# heartrate.net
KiCad netlist of a schematic drawn in EAGLE
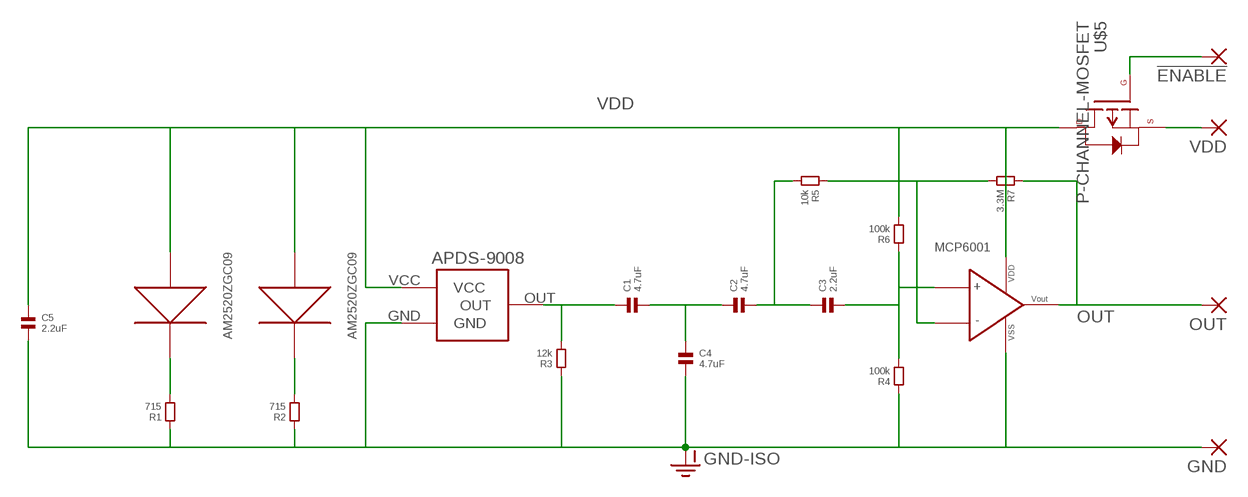
[diagram p0: schematic, sheet 1]

(export (version "E")
  (design (tool "Eeschema 10.0.6"))
  (components
    (comp (ref "!ENABLE")
      (value "SMD2")
      (footprint "eagle-import:SMD1,27-2,54")
      (libsource (lib "eagle-import") (part "SMD2"))
    )
    (comp (ref "C1")
      (value "4.7uF")
      (footprint "eagle-import:0402")
      (libsource (lib "eagle-import") (part "CAPACITOR.0402"))
    )
    (comp (ref "C2")
      (value "4.7uF")
      (footprint "eagle-import:0402")
      (libsource (lib "eagle-import") (part "CAPACITOR.0402"))
    )
    (comp (ref "C3")
      (value "2.2uF")
      (footprint "eagle-import:0402")
      (libsource (lib "eagle-import") (part "CAPACITOR.0402"))
    )
    (comp (ref "C4")
      (value "4.7uF")
      (footprint "eagle-import:0402")
      (libsource (lib "eagle-import") (part "CAPACITOR.0402"))
    )
    (comp (ref "C5")
      (value "2.2uF")
      (footprint "eagle-import:0402")
      (libsource (lib "eagle-import") (part "CAPACITOR.0402"))
    )
    (comp (ref "GND")
      (value "SMD2")
      (footprint "eagle-import:SMD1,27-2,54")
      (libsource (lib "eagle-import") (part "SMD2"))
    )
    (comp (ref "OUT")
      (value "SMD2")
      (footprint "eagle-import:SMD1,27-2,54")
      (libsource (lib "eagle-import") (part "SMD2"))
    )
    (comp (ref "R1")
      (value "715")
      (footprint "eagle-import:0402")
      (libsource (lib "eagle-import") (part "RESISTOR.0402"))
    )
    (comp (ref "R2")
      (value "715")
      (footprint "eagle-import:0402")
      (libsource (lib "eagle-import") (part "RESISTOR.0402"))
    )
    (comp (ref "R3")
      (value "12k")
      (footprint "eagle-import:0402")
      (libsource (lib "eagle-import") (part "RESISTOR.0402"))
    )
    (comp (ref "R4")
      (value "100k")
      (footprint "eagle-import:0402")
      (libsource (lib "eagle-import") (part "RESISTOR.0402"))
    )
    (comp (ref "R5")
      (value "10k")
      (footprint "eagle-import:0402")
      (libsource (lib "eagle-import") (part "RESISTOR.0402"))
    )
    (comp (ref "R6")
      (value "100k")
      (footprint "eagle-import:0402")
      (libsource (lib "eagle-import") (part "RESISTOR.0402"))
    )
    (comp (ref "R7")
      (value "3.3M")
      (footprint "eagle-import:0402")
      (libsource (lib "eagle-import") (part "RESISTOR.0402"))
    )
    (comp (ref "U$1")
      (value "DSAH3717")
      (footprint "eagle-import:DSAH3717")
      (libsource (lib "eagle-import") (part "DSAH3717"))
    )
    (comp (ref "U$2")
      (value "DSAH3717")
      (footprint "eagle-import:DSAH3717")
      (libsource (lib "eagle-import") (part "DSAH3717"))
    )
    (comp (ref "U$3")
      (value "APDS-9008")
      (footprint "eagle-import:APDS-9008")
      (libsource (lib "eagle-import") (part "APDS-9008"))
    )
    (comp (ref "U$4")
      (value "MCP6001")
      (footprint "eagle-import:SOT23-5")
      (libsource (lib "eagle-import") (part "MCP6001"))
    )
    (comp (ref "U$5")
      (value "P-CHANNEL-MOSFET")
      (footprint "eagle-import:SOT23-3")
      (libsource (lib "eagle-import") (part "P-CHANNEL-MOSFET"))
    )
    (comp (ref "VDD")
      (value "SMD2")
      (footprint "eagle-import:SMD1,27-2,54")
      (libsource (lib "eagle-import") (part "SMD2"))
    )
  )
  (nets
    (net (code "1") (name "/OUT") (class "Default")
      (node (ref "OUT") (pin "1") (pinfunction "P_1") (pintype "passive"))
      (node (ref "R7") (pin "1") (pinfunction "1_1") (pintype "bidirectional"))
      (node (ref "U$4") (pin "VOUT") (pinfunction "VOUT_VOUT") (pintype "bidirectional"))
    )
    (net (code "2") (name "/VDD") (class "Default")
      (node (ref "C5") (pin "1") (pinfunction "1_1") (pintype "bidirectional"))
      (node (ref "R6") (pin "2") (pinfunction "2_2") (pintype "bidirectional"))
      (node (ref "U$1") (pin "V") (pinfunction "VDD_V") (pintype "power_in"))
      (node (ref "U$2") (pin "V") (pinfunction "VDD_V") (pintype "power_in"))
      (node (ref "U$3") (pin "VCC") (pinfunction "VCC_VCC") (pintype "bidirectional"))
      (node (ref "U$4") (pin "VDD") (pinfunction "VDD_VDD") (pintype "bidirectional"))
      (node (ref "U$5") (pin "3") (pinfunction "D_3") (pintype "passive"))
    )
    (net (code "3") (name "GND-ISO") (class "Default")
      (node (ref "C4") (pin "2") (pinfunction "2_2") (pintype "bidirectional"))
      (node (ref "C5") (pin "2") (pinfunction "2_2") (pintype "bidirectional"))
      (node (ref "GND") (pin "1") (pinfunction "P_1") (pintype "passive"))
      (node (ref "R1") (pin "1") (pinfunction "1_1") (pintype "bidirectional"))
      (node (ref "R2") (pin "1") (pinfunction "1_1") (pintype "bidirectional"))
      (node (ref "R3") (pin "1") (pinfunction "1_1") (pintype "bidirectional"))
      (node (ref "R4") (pin "1") (pinfunction "1_1") (pintype "bidirectional"))
      (node (ref "U$3") (pin "GND") (pinfunction "GND_GND") (pintype "bidirectional"))
      (node (ref "U$4") (pin "VSS") (pinfunction "VSS_VSS") (pintype "bidirectional"))
    )
    (net (code "4") (name "Net-(!ENABLE-P)") (class "Default")
      (node (ref "!ENABLE") (pin "1") (pinfunction "P_1") (pintype "passive"))
      (node (ref "U$5") (pin "1") (pinfunction "G_1") (pintype "passive"))
    )
    (net (code "5") (name "Net-(C1-Pad1)") (class "Default")
      (node (ref "C1") (pin "1") (pinfunction "1_1") (pintype "bidirectional"))
      (node (ref "R3") (pin "2") (pinfunction "2_2") (pintype "bidirectional"))
      (node (ref "U$3") (pin "OUT") (pinfunction "OUT_OUT") (pintype "bidirectional"))
    )
    (net (code "6") (name "Net-(C1-Pad2)") (class "Default")
      (node (ref "C1") (pin "2") (pinfunction "2_2") (pintype "bidirectional"))
      (node (ref "C2") (pin "1") (pinfunction "1_1") (pintype "bidirectional"))
      (node (ref "C4") (pin "1") (pinfunction "1_1") (pintype "bidirectional"))
    )
    (net (code "7") (name "Net-(C2-Pad2)") (class "Default")
      (node (ref "C2") (pin "2") (pinfunction "2_2") (pintype "bidirectional"))
      (node (ref "C3") (pin "1") (pinfunction "1_1") (pintype "bidirectional"))
      (node (ref "R5") (pin "2") (pinfunction "2_2") (pintype "bidirectional"))
    )
    (net (code "8") (name "Net-(C3-Pad2)") (class "Default")
      (node (ref "C3") (pin "2") (pinfunction "2_2") (pintype "bidirectional"))
      (node (ref "R4") (pin "2") (pinfunction "2_2") (pintype "bidirectional"))
      (node (ref "R6") (pin "1") (pinfunction "1_1") (pintype "bidirectional"))
      (node (ref "U$4") (pin "VIN+") (pinfunction "VIN+_VIN+") (pintype "bidirectional"))
    )
    (net (code "9") (name "Net-(R5-Pad1)") (class "Default")
      (node (ref "R5") (pin "1") (pinfunction "1_1") (pintype "bidirectional"))
      (node (ref "R7") (pin "2") (pinfunction "2_2") (pintype "bidirectional"))
      (node (ref "U$4") (pin "VIN-") (pinfunction "VIN-_VIN-") (pintype "bidirectional"))
    )
    (net (code "10") (name "Net-(U$1-GND)") (class "Default")
      (node (ref "R1") (pin "2") (pinfunction "2_2") (pintype "bidirectional"))
      (node (ref "U$1") (pin "G") (pinfunction "GND_G") (pintype "power_in"))
    )
    (net (code "11") (name "Net-(U$2-GND)") (class "Default")
      (node (ref "R2") (pin "2") (pinfunction "2_2") (pintype "bidirectional"))
      (node (ref "U$2") (pin "G") (pinfunction "GND_G") (pintype "power_in"))
    )
    (net (code "12") (name "Net-(U$5-S)") (class "Default")
      (node (ref "U$5") (pin "2") (pinfunction "S_2") (pintype "passive"))
      (node (ref "VDD") (pin "1") (pinfunction "P_1") (pintype "passive"))
    )
  )
)
